# 909_v1.net
KiCad netlist of a schematic drawn in EAGLE
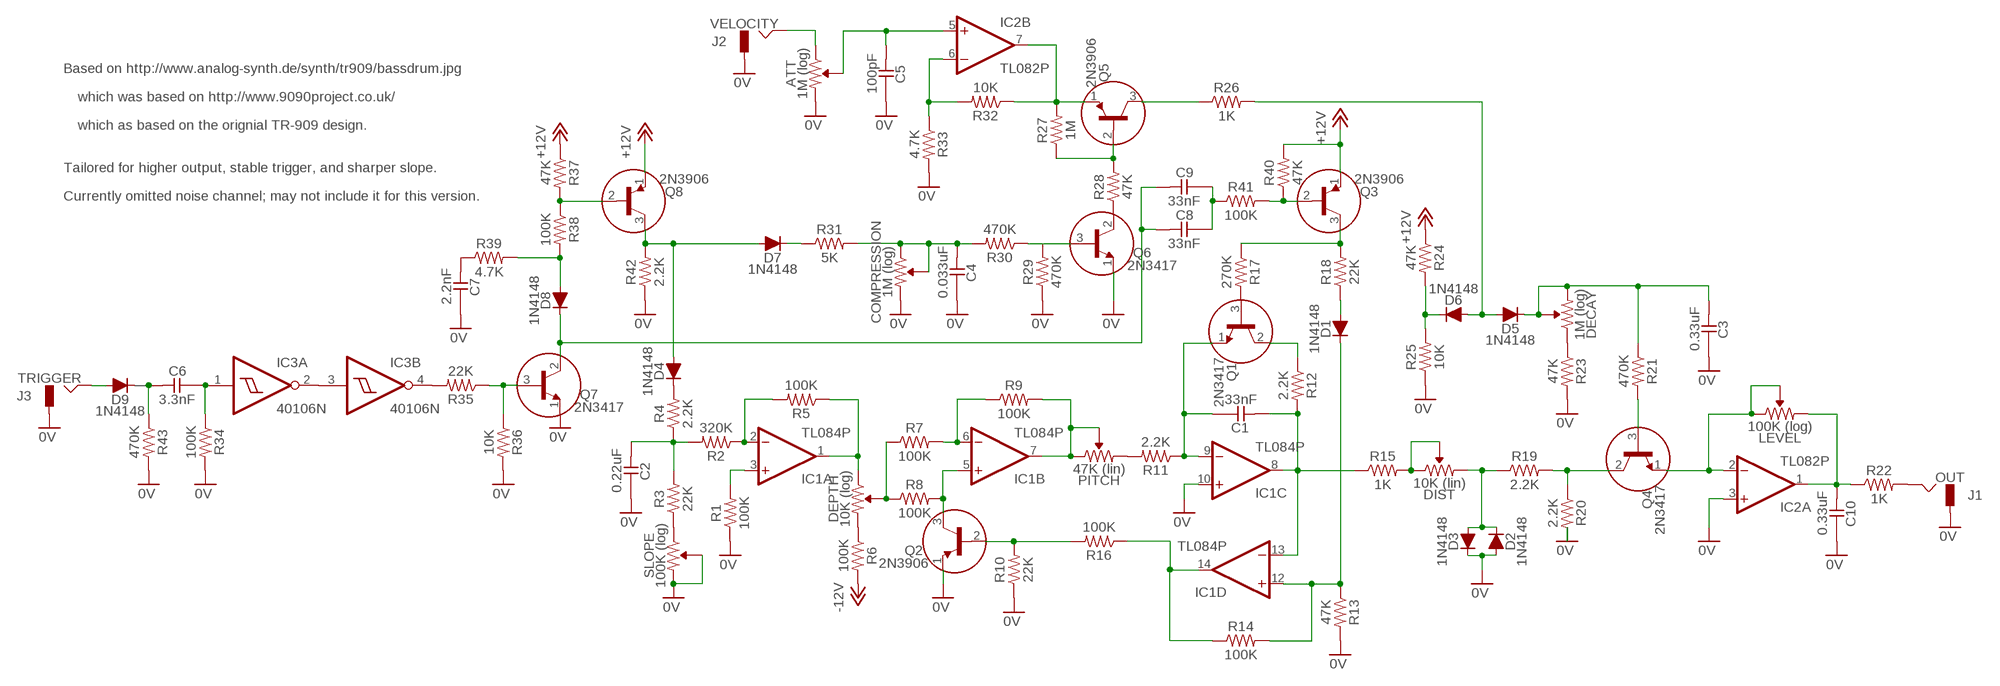
[diagram p0: schematic, sheet 1]

(export (version "E")
  (design (tool "Eeschema 10.0.6"))
  (components
    (comp (ref "ATT")
      (value "1M (log)")
      (footprint "eagle-import:R-VAR")
      (libsource (lib "eagle-import") (part "R-VAR"))
    )
    (comp (ref "C1")
      (value "33nF")
      (footprint "eagle-import:C025-024X044")
      (libsource (lib "eagle-import") (part "CC-US025-024X044"))
    )
    (comp (ref "C2")
      (value "0.22uF")
      (footprint "eagle-import:C025-024X044")
      (libsource (lib "eagle-import") (part "CC-US025-024X044"))
    )
    (comp (ref "C3")
      (value "0.33uF")
      (footprint "eagle-import:C025-024X044")
      (libsource (lib "eagle-import") (part "CC-US025-024X044"))
    )
    (comp (ref "C4")
      (value "0.033uF")
      (footprint "eagle-import:C025-024X044")
      (libsource (lib "eagle-import") (part "CC-US025-024X044"))
    )
    (comp (ref "C5")
      (value "100pF")
      (footprint "eagle-import:C025-024X044")
      (libsource (lib "eagle-import") (part "CC-US025-024X044"))
    )
    (comp (ref "C6")
      (value "3.3nF")
      (footprint "eagle-import:C025-024X044")
      (libsource (lib "eagle-import") (part "CC-US025-024X044"))
    )
    (comp (ref "C7")
      (value "2.2nF")
      (footprint "eagle-import:C025-024X044")
      (libsource (lib "eagle-import") (part "CC-US025-024X044"))
    )
    (comp (ref "C8")
      (value "33nF")
      (footprint "eagle-import:C025-024X044")
      (libsource (lib "eagle-import") (part "CC-US025-024X044"))
    )
    (comp (ref "C9")
      (value "33nF")
      (footprint "eagle-import:C025-024X044")
      (libsource (lib "eagle-import") (part "CC-US025-024X044"))
    )
    (comp (ref "C10")
      (value "0.33uF")
      (footprint "eagle-import:C025-024X044")
      (libsource (lib "eagle-import") (part "CC-US025-024X044"))
    )
    (comp (ref "COMPRESSION")
      (value "1M (log)")
      (footprint "eagle-import:R-VAR")
      (libsource (lib "eagle-import") (part "R-VAR"))
    )
    (comp (ref "D1")
      (value "1N4148")
      (footprint "eagle-import:DO35-7")
      (libsource (lib "eagle-import") (part "1N4148"))
    )
    (comp (ref "D2")
      (value "1N4148")
      (footprint "eagle-import:DO35-7")
      (libsource (lib "eagle-import") (part "1N4148"))
    )
    (comp (ref "D3")
      (value "1N4148")
      (footprint "eagle-import:DO35-7")
      (libsource (lib "eagle-import") (part "1N4148"))
    )
    (comp (ref "D4")
      (value "1N4148")
      (footprint "eagle-import:DO35-7")
      (libsource (lib "eagle-import") (part "1N4148"))
    )
    (comp (ref "D5")
      (value "1N4148")
      (footprint "eagle-import:DO35-7")
      (libsource (lib "eagle-import") (part "1N4148"))
    )
    (comp (ref "D6")
      (value "1N4148")
      (footprint "eagle-import:DO35-7")
      (libsource (lib "eagle-import") (part "1N4148"))
    )
    (comp (ref "D7")
      (value "1N4148")
      (footprint "eagle-import:DO35-7")
      (libsource (lib "eagle-import") (part "1N4148"))
    )
    (comp (ref "D8")
      (value "1N4148")
      (footprint "eagle-import:DO35-7")
      (libsource (lib "eagle-import") (part "1N4148"))
    )
    (comp (ref "D9")
      (value "1N4148")
      (footprint "eagle-import:DO35-7")
      (libsource (lib "eagle-import") (part "1N4148"))
    )
    (comp (ref "DECAY")
      (value "1M (log)")
      (footprint "eagle-import:R-VAR")
      (libsource (lib "eagle-import") (part "R-VAR"))
    )
    (comp (ref "DEPTH")
      (value "10K (log)")
      (footprint "eagle-import:R-VAR")
      (libsource (lib "eagle-import") (part "R-VAR"))
    )
    (comp (ref "DIST")
      (value "10K (lin)")
      (footprint "eagle-import:R-VAR")
      (libsource (lib "eagle-import") (part "R-VAR"))
    )
    (comp (ref "IC1")
      (value "TL084P")
      (footprint "eagle-import:DIL14")
      (libsource (lib "eagle-import") (part "TL084P"))
    )
    (comp (ref "IC2")
      (value "TL082P")
      (footprint "eagle-import:DIL08")
      (libsource (lib "eagle-import") (part "TL082P"))
    )
    (comp (ref "IC3")
      (value "40106N")
      (footprint "eagle-import:DIL14")
      (libsource (lib "eagle-import") (part "40106N"))
    )
    (comp (ref "J1")
      (value "OUT")
      (footprint "eagle-import:JACK-M")
      (libsource (lib "eagle-import") (part "JACK-M"))
    )
    (comp (ref "J2")
      (value "VELOCITY")
      (footprint "eagle-import:JACK-M")
      (libsource (lib "eagle-import") (part "JACK-M"))
    )
    (comp (ref "J3")
      (value "TRIGGER")
      (footprint "eagle-import:JACK-M")
      (libsource (lib "eagle-import") (part "JACK-M"))
    )
    (comp (ref "LEVEL")
      (value "100K (log)")
      (footprint "eagle-import:R-VAR")
      (libsource (lib "eagle-import") (part "R-VAR"))
    )
    (comp (ref "PITCH")
      (value "47K (lin)")
      (footprint "eagle-import:R-VAR")
      (libsource (lib "eagle-import") (part "R-VAR"))
    )
    (comp (ref "Q1")
      (value "2N3417")
      (footprint "eagle-import:TO92")
      (libsource (lib "eagle-import") (part "2N3417"))
    )
    (comp (ref "Q2")
      (value "2N3906")
      (footprint "eagle-import:TO92")
      (libsource (lib "eagle-import") (part "2N3906"))
    )
    (comp (ref "Q3")
      (value "2N3906")
      (footprint "eagle-import:TO92")
      (libsource (lib "eagle-import") (part "2N3906"))
    )
    (comp (ref "Q4")
      (value "2N3417")
      (footprint "eagle-import:TO92")
      (libsource (lib "eagle-import") (part "2N3417"))
    )
    (comp (ref "Q5")
      (value "2N3906")
      (footprint "eagle-import:TO92")
      (libsource (lib "eagle-import") (part "2N3906"))
    )
    (comp (ref "Q6")
      (value "2N3417")
      (footprint "eagle-import:TO92")
      (libsource (lib "eagle-import") (part "2N3417"))
    )
    (comp (ref "Q7")
      (value "2N3417")
      (footprint "eagle-import:TO92")
      (libsource (lib "eagle-import") (part "2N3417"))
    )
    (comp (ref "Q8")
      (value "2N3906")
      (footprint "eagle-import:TO92")
      (libsource (lib "eagle-import") (part "2N3906"))
    )
    (comp (ref "R1")
      (value "100K")
      (footprint "eagle-import:0309_10")
      (libsource (lib "eagle-import") (part "R0309/10"))
    )
    (comp (ref "R2")
      (value "320K")
      (footprint "eagle-import:0309_10")
      (libsource (lib "eagle-import") (part "R0309/10"))
    )
    (comp (ref "R3")
      (value "22K")
      (footprint "eagle-import:0309_10")
      (libsource (lib "eagle-import") (part "R0309/10"))
    )
    (comp (ref "R4")
      (value "2.2K")
      (footprint "eagle-import:0309_10")
      (libsource (lib "eagle-import") (part "R0309/10"))
    )
    (comp (ref "R5")
      (value "100K")
      (footprint "eagle-import:0309_10")
      (libsource (lib "eagle-import") (part "R0309/10"))
    )
    (comp (ref "R6")
      (value "100K")
      (footprint "eagle-import:0309_10")
      (libsource (lib "eagle-import") (part "R0309/10"))
    )
    (comp (ref "R7")
      (value "100K")
      (footprint "eagle-import:0309_10")
      (libsource (lib "eagle-import") (part "R0309/10"))
    )
    (comp (ref "R8")
      (value "100K")
      (footprint "eagle-import:0309_10")
      (libsource (lib "eagle-import") (part "R0309/10"))
    )
    (comp (ref "R9")
      (value "100K")
      (footprint "eagle-import:0309_10")
      (libsource (lib "eagle-import") (part "R0309/10"))
    )
    (comp (ref "R10")
      (value "22K")
      (footprint "eagle-import:0309_10")
      (libsource (lib "eagle-import") (part "R0309/10"))
    )
    (comp (ref "R11")
      (value "2.2K")
      (footprint "eagle-import:0309_10")
      (libsource (lib "eagle-import") (part "R0309/10"))
    )
    (comp (ref "R12")
      (value "2.2K")
      (footprint "eagle-import:0309_10")
      (libsource (lib "eagle-import") (part "R0309/10"))
    )
    (comp (ref "R13")
      (value "47K")
      (footprint "eagle-import:0309_10")
      (libsource (lib "eagle-import") (part "R0309/10"))
    )
    (comp (ref "R14")
      (value "100K")
      (footprint "eagle-import:0309_10")
      (libsource (lib "eagle-import") (part "R0309/10"))
    )
    (comp (ref "R15")
      (value "1K")
      (footprint "eagle-import:0309_10")
      (libsource (lib "eagle-import") (part "R0309/10"))
    )
    (comp (ref "R16")
      (value "100K")
      (footprint "eagle-import:0309_10")
      (libsource (lib "eagle-import") (part "R0309/10"))
    )
    (comp (ref "R17")
      (value "270K")
      (footprint "eagle-import:0309_10")
      (libsource (lib "eagle-import") (part "R0309/10"))
    )
    (comp (ref "R18")
      (value "22K")
      (footprint "eagle-import:0309_10")
      (libsource (lib "eagle-import") (part "R0309/10"))
    )
    (comp (ref "R19")
      (value "2.2K")
      (footprint "eagle-import:0309_10")
      (libsource (lib "eagle-import") (part "R0309/10"))
    )
    (comp (ref "R20")
      (value "2.2K")
      (footprint "eagle-import:0309_10")
      (libsource (lib "eagle-import") (part "R0309/10"))
    )
    (comp (ref "R21")
      (value "470K")
      (footprint "eagle-import:0309_10")
      (libsource (lib "eagle-import") (part "R0309/10"))
    )
    (comp (ref "R22")
      (value "1K")
      (footprint "eagle-import:0309_10")
      (libsource (lib "eagle-import") (part "R0309/10"))
    )
    (comp (ref "R23")
      (value "47K")
      (footprint "eagle-import:0309_10")
      (libsource (lib "eagle-import") (part "R0309/10"))
    )
    (comp (ref "R24")
      (value "47K")
      (footprint "eagle-import:0309_10")
      (libsource (lib "eagle-import") (part "R0309/10"))
    )
    (comp (ref "R25")
      (value "10K")
      (footprint "eagle-import:0309_10")
      (libsource (lib "eagle-import") (part "R0309/10"))
    )
    (comp (ref "R26")
      (value "1K")
      (footprint "eagle-import:0309_10")
      (libsource (lib "eagle-import") (part "R0309/10"))
    )
    (comp (ref "R27")
      (value "1M")
      (footprint "eagle-import:0309_10")
      (libsource (lib "eagle-import") (part "R0309/10"))
    )
    (comp (ref "R28")
      (value "47K")
      (footprint "eagle-import:0309_10")
      (libsource (lib "eagle-import") (part "R0309/10"))
    )
    (comp (ref "R29")
      (value "470K")
      (footprint "eagle-import:0309_10")
      (libsource (lib "eagle-import") (part "R0309/10"))
    )
    (comp (ref "R30")
      (value "470K")
      (footprint "eagle-import:0309_10")
      (libsource (lib "eagle-import") (part "R0309/10"))
    )
    (comp (ref "R31")
      (value "5K")
      (footprint "eagle-import:0309_10")
      (libsource (lib "eagle-import") (part "R0309/10"))
    )
    (comp (ref "R32")
      (value "10K")
      (footprint "eagle-import:0309_10")
      (libsource (lib "eagle-import") (part "R0309/10"))
    )
    (comp (ref "R33")
      (value "4.7K")
      (footprint "eagle-import:0309_10")
      (libsource (lib "eagle-import") (part "R0309/10"))
    )
    (comp (ref "R34")
      (value "100K")
      (footprint "eagle-import:0309_10")
      (libsource (lib "eagle-import") (part "R0309/10"))
    )
    (comp (ref "R35")
      (value "22K")
      (footprint "eagle-import:0309_10")
      (libsource (lib "eagle-import") (part "R0309/10"))
    )
    (comp (ref "R36")
      (value "10K")
      (footprint "eagle-import:0309_10")
      (libsource (lib "eagle-import") (part "R0309/10"))
    )
    (comp (ref "R37")
      (value "47K")
      (footprint "eagle-import:0309_10")
      (libsource (lib "eagle-import") (part "R0309/10"))
    )
    (comp (ref "R38")
      (value "100K")
      (footprint "eagle-import:0309_10")
      (libsource (lib "eagle-import") (part "R0309/10"))
    )
    (comp (ref "R39")
      (value "4.7K")
      (footprint "eagle-import:0309_10")
      (libsource (lib "eagle-import") (part "R0309/10"))
    )
    (comp (ref "R40")
      (value "47K")
      (footprint "eagle-import:0309_10")
      (libsource (lib "eagle-import") (part "R0309/10"))
    )
    (comp (ref "R41")
      (value "100K")
      (footprint "eagle-import:0309_10")
      (libsource (lib "eagle-import") (part "R0309/10"))
    )
    (comp (ref "R42")
      (value "2.2K")
      (footprint "eagle-import:0309_10")
      (libsource (lib "eagle-import") (part "R0309/10"))
    )
    (comp (ref "R43")
      (value "470K")
      (footprint "eagle-import:0309_10")
      (libsource (lib "eagle-import") (part "R0309/10"))
    )
    (comp (ref "SLOPE")
      (value "100K (log)")
      (footprint "eagle-import:R-VAR")
      (libsource (lib "eagle-import") (part "R-VAR"))
    )
  )
  (nets
    (net (code "1") (name "+12V") (class "Default")
      (node (ref "Q3") (pin "1") (pinfunction "E_1") (pintype "passive"))
      (node (ref "Q8") (pin "1") (pinfunction "E_1") (pintype "passive"))
      (node (ref "R24") (pin "1") (pinfunction "1_1") (pintype "passive"))
      (node (ref "R37") (pin "1") (pinfunction "1_1") (pintype "passive"))
      (node (ref "R40") (pin "2") (pinfunction "2_2") (pintype "passive"))
    )
    (net (code "2") (name "-12V") (class "Default")
      (node (ref "R6") (pin "2") (pinfunction "2_2") (pintype "passive"))
    )
    (net (code "3") (name "0V") (class "Default")
      (node (ref "ATT") (pin "R2") (pinfunction "2_R2") (pintype "passive"))
      (node (ref "C10") (pin "1") (pinfunction "1_1") (pintype "passive"))
      (node (ref "C2") (pin "1") (pinfunction "1_1") (pintype "passive"))
      (node (ref "C3") (pin "1") (pinfunction "1_1") (pintype "passive"))
      (node (ref "C4") (pin "1") (pinfunction "1_1") (pintype "passive"))
      (node (ref "C5") (pin "1") (pinfunction "1_1") (pintype "passive"))
      (node (ref "C7") (pin "1") (pinfunction "1_1") (pintype "passive"))
      (node (ref "COMPRESSION") (pin "R2") (pinfunction "2_R2") (pintype "passive"))
      (node (ref "D2") (pin "A") (pinfunction "A_A") (pintype "passive"))
      (node (ref "D3") (pin "C") (pinfunction "C_C") (pintype "passive"))
      (node (ref "IC1") (pin "10") (pinfunction "+IN_10") (pintype "input"))
      (node (ref "IC2") (pin "3") (pinfunction "+IN_3") (pintype "input"))
      (node (ref "J1") (pin "GND") (pinfunction "GND_GND") (pintype "bidirectional"))
      (node (ref "J2") (pin "GND") (pinfunction "GND_GND") (pintype "bidirectional"))
      (node (ref "J3") (pin "GND") (pinfunction "GND_GND") (pintype "bidirectional"))
      (node (ref "Q2") (pin "1") (pinfunction "E_1") (pintype "passive"))
      (node (ref "Q6") (pin "1") (pinfunction "E_1") (pintype "passive"))
      (node (ref "Q7") (pin "1") (pinfunction "E_1") (pintype "passive"))
      (node (ref "R1") (pin "1") (pinfunction "1_1") (pintype "passive"))
      (node (ref "R10") (pin "1") (pinfunction "1_1") (pintype "passive"))
      (node (ref "R13") (pin "2") (pinfunction "2_2") (pintype "passive"))
      (node (ref "R20") (pin "2") (pinfunction "2_2") (pintype "passive"))
      (node (ref "R23") (pin "2") (pinfunction "2_2") (pintype "passive"))
      (node (ref "R25") (pin "1") (pinfunction "1_1") (pintype "passive"))
      (node (ref "R29") (pin "1") (pinfunction "1_1") (pintype "passive"))
      (node (ref "R33") (pin "2") (pinfunction "2_2") (pintype "passive"))
      (node (ref "R34") (pin "2") (pinfunction "2_2") (pintype "passive"))
      (node (ref "R36") (pin "2") (pinfunction "2_2") (pintype "passive"))
      (node (ref "R42") (pin "1") (pinfunction "1_1") (pintype "passive"))
      (node (ref "R43") (pin "2") (pinfunction "2_2") (pintype "passive"))
      (node (ref "SLOPE") (pin "R2") (pinfunction "2_R2") (pintype "passive"))
      (node (ref "SLOPE") (pin "VAR") (pinfunction "P$1_VAR") (pintype "passive"))
    )
    (net (code "4") (name "Net-(ATT-1)") (class "Default")
      (node (ref "ATT") (pin "R1") (pinfunction "1_R1") (pintype "passive"))
      (node (ref "J2") (pin "HOT") (pinfunction "HOT_HOT") (pintype "bidirectional"))
    )
    (net (code "5") (name "Net-(ATT-P$1)") (class "Default")
      (node (ref "ATT") (pin "VAR") (pinfunction "P$1_VAR") (pintype "passive"))
      (node (ref "C5") (pin "2") (pinfunction "2_2") (pintype "passive"))
      (node (ref "IC2") (pin "5") (pinfunction "+IN_5") (pintype "input"))
    )
    (net (code "6") (name "Net-(C2-Pad2)") (class "Default")
      (node (ref "C2") (pin "2") (pinfunction "2_2") (pintype "passive"))
      (node (ref "R2") (pin "2") (pinfunction "2_2") (pintype "passive"))
      (node (ref "R3") (pin "2") (pinfunction "2_2") (pintype "passive"))
      (node (ref "R4") (pin "1") (pinfunction "1_1") (pintype "passive"))
    )
    (net (code "7") (name "Net-(C6-Pad2)") (class "Default")
      (node (ref "C6") (pin "2") (pinfunction "2_2") (pintype "passive"))
      (node (ref "R43") (pin "1") (pinfunction "1_1") (pintype "passive"))
    )
    (net (code "8") (name "Net-(C7-Pad2)") (class "Default")
      (node (ref "C7") (pin "2") (pinfunction "2_2") (pintype "passive"))
      (node (ref "R39") (pin "1") (pinfunction "1_1") (pintype "passive"))
    )
    (net (code "9") (name "Net-(C8-Pad1)") (class "Default")
      (node (ref "C8") (pin "1") (pinfunction "1_1") (pintype "passive"))
      (node (ref "C9") (pin "1") (pinfunction "1_1") (pintype "passive"))
      (node (ref "R41") (pin "1") (pinfunction "1_1") (pintype "passive"))
    )
    (net (code "10") (name "Net-(COMPRESSION-1)") (class "Default")
      (node (ref "C4") (pin "2") (pinfunction "2_2") (pintype "passive"))
      (node (ref "COMPRESSION") (pin "R1") (pinfunction "1_R1") (pintype "passive"))
      (node (ref "COMPRESSION") (pin "VAR") (pinfunction "P$1_VAR") (pintype "passive"))
      (node (ref "R30") (pin "2") (pinfunction "2_2") (pintype "passive"))
      (node (ref "R31") (pin "2") (pinfunction "2_2") (pintype "passive"))
    )
    (net (code "11") (name "Net-(D1-PadA)") (class "Default")
      (node (ref "D1") (pin "A") (pinfunction "A_A") (pintype "passive"))
      (node (ref "R18") (pin "1") (pinfunction "1_1") (pintype "passive"))
    )
    (net (code "12") (name "Net-(D4-PadC)") (class "Default")
      (node (ref "D4") (pin "C") (pinfunction "C_C") (pintype "passive"))
      (node (ref "R4") (pin "2") (pinfunction "2_2") (pintype "passive"))
    )
    (net (code "13") (name "Net-(D5-PadA)") (class "Default")
      (node (ref "D5") (pin "A") (pinfunction "A_A") (pintype "passive"))
      (node (ref "D6") (pin "A") (pinfunction "A_A") (pintype "passive"))
      (node (ref "R26") (pin "2") (pinfunction "2_2") (pintype "passive"))
    )
    (net (code "14") (name "Net-(D6-PadC)") (class "Default")
      (node (ref "D6") (pin "C") (pinfunction "C_C") (pintype "passive"))
      (node (ref "R24") (pin "2") (pinfunction "2_2") (pintype "passive"))
      (node (ref "R25") (pin "2") (pinfunction "2_2") (pintype "passive"))
    )
    (net (code "15") (name "Net-(D7-PadC)") (class "Default")
      (node (ref "D7") (pin "C") (pinfunction "C_C") (pintype "passive"))
      (node (ref "R31") (pin "1") (pinfunction "1_1") (pintype "passive"))
    )
    (net (code "16") (name "Net-(D8-PadA)") (class "Default")
      (node (ref "D8") (pin "A") (pinfunction "A_A") (pintype "passive"))
      (node (ref "R38") (pin "2") (pinfunction "2_2") (pintype "passive"))
      (node (ref "R39") (pin "2") (pinfunction "2_2") (pintype "passive"))
    )
    (net (code "17") (name "Net-(D9-PadA)") (class "Default")
      (node (ref "D9") (pin "A") (pinfunction "A_A") (pintype "passive"))
      (node (ref "J3") (pin "HOT") (pinfunction "HOT_HOT") (pintype "bidirectional"))
    )
    (net (code "18") (name "Net-(DECAY-1)") (class "Default")
      (node (ref "DECAY") (pin "R1") (pinfunction "1_R1") (pintype "passive"))
      (node (ref "R23") (pin "1") (pinfunction "1_1") (pintype "passive"))
    )
    (net (code "19") (name "Net-(DECAY-2)") (class "Default")
      (node (ref "C3") (pin "2") (pinfunction "2_2") (pintype "passive"))
      (node (ref "D5") (pin "C") (pinfunction "C_C") (pintype "passive"))
      (node (ref "DECAY") (pin "R2") (pinfunction "2_R2") (pintype "passive"))
      (node (ref "DECAY") (pin "VAR") (pinfunction "P$1_VAR") (pintype "passive"))
      (node (ref "R21") (pin "1") (pinfunction "1_1") (pintype "passive"))
    )
    (net (code "20") (name "Net-(DEPTH-1)") (class "Default")
      (node (ref "DEPTH") (pin "R1") (pinfunction "1_R1") (pintype "passive"))
      (node (ref "IC1") (pin "1") (pinfunction "OUT_1") (pintype "output"))
      (node (ref "R5") (pin "1") (pinfunction "1_1") (pintype "passive"))
    )
    (net (code "21") (name "Net-(DEPTH-2)") (class "Default")
      (node (ref "DEPTH") (pin "R2") (pinfunction "2_R2") (pintype "passive"))
      (node (ref "R6") (pin "1") (pinfunction "1_1") (pintype "passive"))
    )
    (net (code "22") (name "Net-(DEPTH-P$1)") (class "Default")
      (node (ref "DEPTH") (pin "VAR") (pinfunction "P$1_VAR") (pintype "passive"))
      (node (ref "R7") (pin "1") (pinfunction "1_1") (pintype "passive"))
      (node (ref "R8") (pin "1") (pinfunction "1_1") (pintype "passive"))
    )
    (net (code "23") (name "Net-(DIST-1)") (class "Default")
      (node (ref "DIST") (pin "R1") (pinfunction "1_R1") (pintype "passive"))
      (node (ref "DIST") (pin "VAR") (pinfunction "P$1_VAR") (pintype "passive"))
      (node (ref "R15") (pin "2") (pinfunction "2_2") (pintype "passive"))
    )
    (net (code "24") (name "Net-(DIST-2)") (class "Default")
      (node (ref "D2") (pin "C") (pinfunction "C_C") (pintype "passive"))
      (node (ref "D3") (pin "A") (pinfunction "A_A") (pintype "passive"))
      (node (ref "DIST") (pin "R2") (pinfunction "2_R2") (pintype "passive"))
      (node (ref "R19") (pin "1") (pinfunction "1_1") (pintype "passive"))
    )
    (net (code "25") (name "Net-(IC1A-+IN)") (class "Default")
      (node (ref "IC1") (pin "3") (pinfunction "+IN_3") (pintype "input"))
      (node (ref "R1") (pin "2") (pinfunction "2_2") (pintype "passive"))
    )
    (net (code "26") (name "Net-(IC1A--IN)") (class "Default")
      (node (ref "IC1") (pin "2") (pinfunction "-IN_2") (pintype "input"))
      (node (ref "R2") (pin "1") (pinfunction "1_1") (pintype "passive"))
      (node (ref "R5") (pin "2") (pinfunction "2_2") (pintype "passive"))
    )
    (net (code "27") (name "Net-(IC1B-+IN)") (class "Default")
      (node (ref "IC1") (pin "5") (pinfunction "+IN_5") (pintype "input"))
      (node (ref "Q2") (pin "3") (pinfunction "C_3") (pintype "passive"))
      (node (ref "R8") (pin "2") (pinfunction "2_2") (pintype "passive"))
    )
    (net (code "28") (name "Net-(IC1B--IN)") (class "Default")
      (node (ref "IC1") (pin "6") (pinfunction "-IN_6") (pintype "input"))
      (node (ref "R7") (pin "2") (pinfunction "2_2") (pintype "passive"))
      (node (ref "R9") (pin "1") (pinfunction "1_1") (pintype "passive"))
    )
    (net (code "29") (name "Net-(IC1B-OUT)") (class "Default")
      (node (ref "IC1") (pin "7") (pinfunction "OUT_7") (pintype "output"))
      (node (ref "PITCH") (pin "R1") (pinfunction "1_R1") (pintype "passive"))
      (node (ref "PITCH") (pin "VAR") (pinfunction "P$1_VAR") (pintype "passive"))
      (node (ref "R9") (pin "2") (pinfunction "2_2") (pintype "passive"))
    )
    (net (code "30") (name "Net-(IC1C--IN)") (class "Default")
      (node (ref "C1") (pin "1") (pinfunction "1_1") (pintype "passive"))
      (node (ref "IC1") (pin "9") (pinfunction "-IN_9") (pintype "input"))
      (node (ref "Q1") (pin "1") (pinfunction "E_1") (pintype "passive"))
      (node (ref "R11") (pin "1") (pinfunction "1_1") (pintype "passive"))
    )
    (net (code "31") (name "Net-(IC1C-OUT)") (class "Default")
      (node (ref "C1") (pin "2") (pinfunction "2_2") (pintype "passive"))
      (node (ref "IC1") (pin "13") (pinfunction "-IN_13") (pintype "input"))
      (node (ref "IC1") (pin "8") (pinfunction "OUT_8") (pintype "output"))
      (node (ref "R12") (pin "2") (pinfunction "2_2") (pintype "passive"))
      (node (ref "R15") (pin "1") (pinfunction "1_1") (pintype "passive"))
    )
    (net (code "32") (name "Net-(IC1D-+IN)") (class "Default")
      (node (ref "D1") (pin "C") (pinfunction "C_C") (pintype "passive"))
      (node (ref "IC1") (pin "12") (pinfunction "+IN_12") (pintype "input"))
      (node (ref "R13") (pin "1") (pinfunction "1_1") (pintype "passive"))
      (node (ref "R14") (pin "2") (pinfunction "2_2") (pintype "passive"))
    )
    (net (code "33") (name "Net-(IC1D-OUT)") (class "Default")
      (node (ref "IC1") (pin "14") (pinfunction "OUT_14") (pintype "output"))
      (node (ref "R14") (pin "1") (pinfunction "1_1") (pintype "passive"))
      (node (ref "R16") (pin "1") (pinfunction "1_1") (pintype "passive"))
    )
    (net (code "34") (name "Net-(IC2A--IN)") (class "Default")
      (node (ref "IC2") (pin "2") (pinfunction "-IN_2") (pintype "input"))
      (node (ref "LEVEL") (pin "R1") (pinfunction "1_R1") (pintype "passive"))
      (node (ref "LEVEL") (pin "VAR") (pinfunction "P$1_VAR") (pintype "passive"))
      (node (ref "Q4") (pin "1") (pinfunction "E_1") (pintype "passive"))
    )
    (net (code "35") (name "Net-(IC2A-OUT)") (class "Default")
      (node (ref "C10") (pin "2") (pinfunction "2_2") (pintype "passive"))
      (node (ref "IC2") (pin "1") (pinfunction "OUT_1") (pintype "output"))
      (node (ref "LEVEL") (pin "R2") (pinfunction "2_R2") (pintype "passive"))
      (node (ref "R22") (pin "1") (pinfunction "1_1") (pintype "passive"))
    )
    (net (code "36") (name "Net-(IC2B--IN)") (class "Default")
      (node (ref "IC2") (pin "6") (pinfunction "-IN_6") (pintype "input"))
      (node (ref "R32") (pin "2") (pinfunction "2_2") (pintype "passive"))
      (node (ref "R33") (pin "1") (pinfunction "1_1") (pintype "passive"))
    )
    (net (code "37") (name "Net-(IC2B-OUT)") (class "Default")
      (node (ref "IC2") (pin "7") (pinfunction "OUT_7") (pintype "output"))
      (node (ref "Q5") (pin "1") (pinfunction "E_1") (pintype "passive"))
      (node (ref "R27") (pin "2") (pinfunction "2_2") (pintype "passive"))
      (node (ref "R32") (pin "1") (pinfunction "1_1") (pintype "passive"))
    )
    (net (code "38") (name "Net-(IC3A-I)") (class "Default")
      (node (ref "C6") (pin "1") (pinfunction "1_1") (pintype "passive"))
      (node (ref "IC3") (pin "1") (pinfunction "I_1") (pintype "input"))
      (node (ref "R34") (pin "1") (pinfunction "1_1") (pintype "passive"))
    )
    (net (code "39") (name "Net-(IC3A-O)") (class "Default")
      (node (ref "IC3") (pin "2") (pinfunction "O_2") (pintype "output"))
      (node (ref "IC3") (pin "3") (pinfunction "I_3") (pintype "input"))
    )
    (net (code "40") (name "Net-(IC3B-O)") (class "Default")
      (node (ref "IC3") (pin "4") (pinfunction "O_4") (pintype "output"))
      (node (ref "R35") (pin "2") (pinfunction "2_2") (pintype "passive"))
    )
    (net (code "41") (name "Net-(J1-PadHOT)") (class "Default")
      (node (ref "J1") (pin "HOT") (pinfunction "HOT_HOT") (pintype "bidirectional"))
      (node (ref "R22") (pin "2") (pinfunction "2_2") (pintype "passive"))
    )
    (net (code "42") (name "Net-(PITCH-2)") (class "Default")
      (node (ref "PITCH") (pin "R2") (pinfunction "2_R2") (pintype "passive"))
      (node (ref "R11") (pin "2") (pinfunction "2_2") (pintype "passive"))
    )
    (net (code "43") (name "Net-(Q1-B)") (class "Default")
      (node (ref "Q1") (pin "3") (pinfunction "B_3") (pintype "passive"))
      (node (ref "R17") (pin "2") (pinfunction "2_2") (pintype "passive"))
    )
    (net (code "44") (name "Net-(Q1-C)") (class "Default")
      (node (ref "Q1") (pin "2") (pinfunction "C_2") (pintype "passive"))
      (node (ref "R12") (pin "1") (pinfunction "1_1") (pintype "passive"))
    )
    (net (code "45") (name "Net-(Q2-B)") (class "Default")
      (node (ref "Q2") (pin "2") (pinfunction "B_2") (pintype "passive"))
      (node (ref "R10") (pin "2") (pinfunction "2_2") (pintype "passive"))
      (node (ref "R16") (pin "2") (pinfunction "2_2") (pintype "passive"))
    )
    (net (code "46") (name "Net-(Q3-B)") (class "Default")
      (node (ref "Q3") (pin "2") (pinfunction "B_2") (pintype "passive"))
      (node (ref "R40") (pin "1") (pinfunction "1_1") (pintype "passive"))
      (node (ref "R41") (pin "2") (pinfunction "2_2") (pintype "passive"))
    )
    (net (code "47") (name "Net-(Q3-C)") (class "Default")
      (node (ref "Q3") (pin "3") (pinfunction "C_3") (pintype "passive"))
      (node (ref "R17") (pin "1") (pinfunction "1_1") (pintype "passive"))
      (node (ref "R18") (pin "2") (pinfunction "2_2") (pintype "passive"))
    )
    (net (code "48") (name "Net-(Q4-B)") (class "Default")
      (node (ref "Q4") (pin "3") (pinfunction "B_3") (pintype "passive"))
      (node (ref "R21") (pin "2") (pinfunction "2_2") (pintype "passive"))
    )
    (net (code "49") (name "Net-(Q4-C)") (class "Default")
      (node (ref "Q4") (pin "2") (pinfunction "C_2") (pintype "passive"))
      (node (ref "R19") (pin "2") (pinfunction "2_2") (pintype "passive"))
      (node (ref "R20") (pin "1") (pinfunction "1_1") (pintype "passive"))
    )
    (net (code "50") (name "Net-(Q5-B)") (class "Default")
      (node (ref "Q5") (pin "2") (pinfunction "B_2") (pintype "passive"))
      (node (ref "R27") (pin "1") (pinfunction "1_1") (pintype "passive"))
      (node (ref "R28") (pin "2") (pinfunction "2_2") (pintype "passive"))
    )
    (net (code "51") (name "Net-(Q5-C)") (class "Default")
      (node (ref "Q5") (pin "3") (pinfunction "C_3") (pintype "passive"))
      (node (ref "R26") (pin "1") (pinfunction "1_1") (pintype "passive"))
    )
    (net (code "52") (name "Net-(Q6-B)") (class "Default")
      (node (ref "Q6") (pin "3") (pinfunction "B_3") (pintype "passive"))
      (node (ref "R29") (pin "2") (pinfunction "2_2") (pintype "passive"))
      (node (ref "R30") (pin "1") (pinfunction "1_1") (pintype "passive"))
    )
    (net (code "53") (name "Net-(Q6-C)") (class "Default")
      (node (ref "Q6") (pin "2") (pinfunction "C_2") (pintype "passive"))
      (node (ref "R28") (pin "1") (pinfunction "1_1") (pintype "passive"))
    )
    (net (code "54") (name "Net-(Q7-B)") (class "Default")
      (node (ref "Q7") (pin "3") (pinfunction "B_3") (pintype "passive"))
      (node (ref "R35") (pin "1") (pinfunction "1_1") (pintype "passive"))
      (node (ref "R36") (pin "1") (pinfunction "1_1") (pintype "passive"))
    )
    (net (code "55") (name "Net-(Q7-C)") (class "Default")
      (node (ref "C8") (pin "2") (pinfunction "2_2") (pintype "passive"))
      (node (ref "C9") (pin "2") (pinfunction "2_2") (pintype "passive"))
      (node (ref "D8") (pin "C") (pinfunction "C_C") (pintype "passive"))
      (node (ref "Q7") (pin "2") (pinfunction "C_2") (pintype "passive"))
    )
    (net (code "56") (name "Net-(Q8-B)") (class "Default")
      (node (ref "Q8") (pin "2") (pinfunction "B_2") (pintype "passive"))
      (node (ref "R37") (pin "2") (pinfunction "2_2") (pintype "passive"))
      (node (ref "R38") (pin "1") (pinfunction "1_1") (pintype "passive"))
    )
    (net (code "57") (name "Net-(Q8-C)") (class "Default")
      (node (ref "D4") (pin "A") (pinfunction "A_A") (pintype "passive"))
      (node (ref "D7") (pin "A") (pinfunction "A_A") (pintype "passive"))
      (node (ref "Q8") (pin "3") (pinfunction "C_3") (pintype "passive"))
      (node (ref "R42") (pin "2") (pinfunction "2_2") (pintype "passive"))
    )
    (net (code "58") (name "Net-(SLOPE-1)") (class "Default")
      (node (ref "R3") (pin "1") (pinfunction "1_1") (pintype "passive"))
      (node (ref "SLOPE") (pin "R1") (pinfunction "1_R1") (pintype "passive"))
    )
    (net (code "59") (name "unconnected-(D9-PadC)") (class "Default")
      (node (ref "D9") (pin "C") (pinfunction "C_C") (pintype "passive"))
    )
  )
)
